# HoodBoard_V1.net
KiCad netlist of a schematic drawn in EAGLE
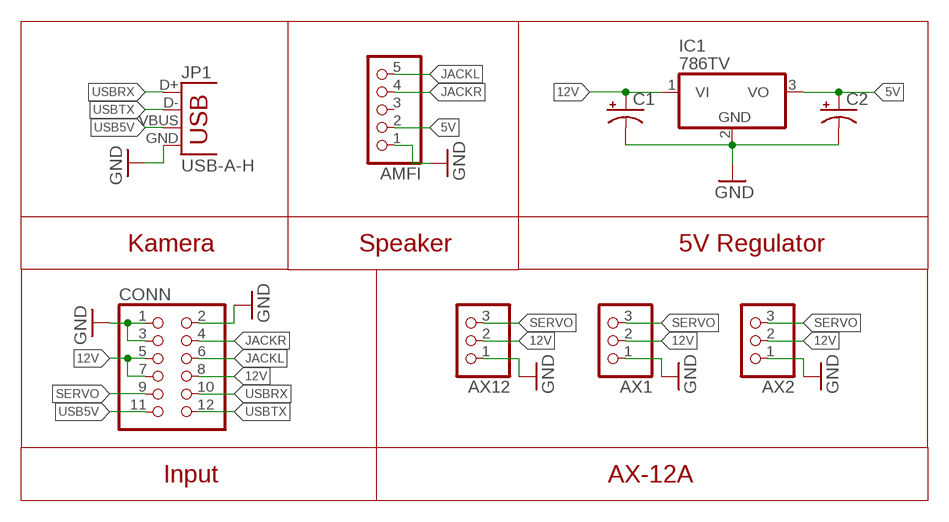
[diagram p0: schematic, sheet 1]

(export (version "E")
  (design (tool "Eeschema 10.0.6"))
  (components
    (comp (ref "AMFI")
      (value "PINHD-1X5")
      (footprint "eagle-import:1X05")
      (libsource (lib "eagle-import") (part "PINHD-1X5"))
    )
    (comp (ref "AX1")
      (value "PINHD-1X3")
      (footprint "eagle-import:1X03")
      (libsource (lib "eagle-import") (part "PINHD-1X3"))
    )
    (comp (ref "AX2")
      (value "PINHD-1X3")
      (footprint "eagle-import:1X03")
      (libsource (lib "eagle-import") (part "PINHD-1X3"))
    )
    (comp (ref "AX12")
      (value "PINHD-1X3")
      (footprint "eagle-import:1X03")
      (libsource (lib "eagle-import") (part "PINHD-1X3"))
    )
    (comp (ref "C1")
      (value "10UF-25V-20%(PTH)")
      (footprint "eagle-import:CPOL-RADIAL-10UF-25V")
      (libsource (lib "eagle-import") (part "10UF-25V-20%(PTH)"))
    )
    (comp (ref "C2")
      (value "10UF-25V-20%(PTH)")
      (footprint "eagle-import:CPOL-RADIAL-10UF-25V")
      (libsource (lib "eagle-import") (part "10UF-25V-20%(PTH)"))
    )
    (comp (ref "CONN")
      (value "PINHD-2X6")
      (footprint "eagle-import:2X06")
      (libsource (lib "eagle-import") (part "PINHD-2X6"))
    )
    (comp (ref "IC1")
      (value "786TV")
      (footprint "eagle-import:TO220V")
      (libsource (lib "eagle-import") (part "78TV6"))
    )
    (comp (ref "JP1")
      (value "USB-A-H")
      (footprint "eagle-import:USB-A-H")
      (libsource (lib "eagle-import") (part "USB-A-H"))
    )
  )
  (nets
    (net (code "1") (name "5V") (class "Default")
      (node (ref "AMFI") (pin "2") (pinfunction "2_2") (pintype "passive"))
      (node (ref "C2") (pin "1") (pinfunction "+_1") (pintype "passive"))
      (node (ref "IC1") (pin "3") (pinfunction "VO_3") (pintype "passive"))
    )
    (net (code "2") (name "12V") (class "Default")
      (node (ref "AX1") (pin "2") (pinfunction "2_2") (pintype "passive"))
      (node (ref "AX12") (pin "2") (pinfunction "2_2") (pintype "passive"))
      (node (ref "AX2") (pin "2") (pinfunction "2_2") (pintype "passive"))
      (node (ref "C1") (pin "1") (pinfunction "+_1") (pintype "passive"))
      (node (ref "CONN") (pin "5") (pinfunction "5_5") (pintype "passive"))
      (node (ref "CONN") (pin "7") (pinfunction "7_7") (pintype "passive"))
      (node (ref "CONN") (pin "8") (pinfunction "8_8") (pintype "passive"))
      (node (ref "IC1") (pin "1") (pinfunction "VI_1") (pintype "input"))
    )
    (net (code "3") (name "GND") (class "Default")
      (node (ref "AMFI") (pin "1") (pinfunction "1_1") (pintype "passive"))
      (node (ref "AX1") (pin "1") (pinfunction "1_1") (pintype "passive"))
      (node (ref "AX12") (pin "1") (pinfunction "1_1") (pintype "passive"))
      (node (ref "AX2") (pin "1") (pinfunction "1_1") (pintype "passive"))
      (node (ref "C1") (pin "2") (pinfunction "-_2") (pintype "passive"))
      (node (ref "C2") (pin "2") (pinfunction "-_2") (pintype "passive"))
      (node (ref "CONN") (pin "1") (pinfunction "1_1") (pintype "passive"))
      (node (ref "CONN") (pin "2") (pinfunction "2_2") (pintype "passive"))
      (node (ref "CONN") (pin "3") (pinfunction "3_3") (pintype "passive"))
      (node (ref "IC1") (pin "2") (pinfunction "GND_2") (pintype "passive"))
      (node (ref "JP1") (pin "GND") (pinfunction "GND_GND") (pintype "bidirectional"))
    )
    (net (code "4") (name "JACKL") (class "Default")
      (node (ref "AMFI") (pin "5") (pinfunction "5_5") (pintype "passive"))
      (node (ref "CONN") (pin "6") (pinfunction "6_6") (pintype "passive"))
    )
    (net (code "5") (name "JACKR") (class "Default")
      (node (ref "AMFI") (pin "4") (pinfunction "4_4") (pintype "passive"))
      (node (ref "CONN") (pin "4") (pinfunction "4_4") (pintype "passive"))
    )
    (net (code "6") (name "SERVO") (class "Default")
      (node (ref "AX1") (pin "3") (pinfunction "3_3") (pintype "passive"))
      (node (ref "AX12") (pin "3") (pinfunction "3_3") (pintype "passive"))
      (node (ref "AX2") (pin "3") (pinfunction "3_3") (pintype "passive"))
      (node (ref "CONN") (pin "9") (pinfunction "9_9") (pintype "passive"))
    )
    (net (code "7") (name "USB5V") (class "Default")
      (node (ref "CONN") (pin "11") (pinfunction "11_11") (pintype "passive"))
      (node (ref "JP1") (pin "VBUS") (pinfunction "VBUS_VBUS") (pintype "bidirectional"))
    )
    (net (code "8") (name "USBRX") (class "Default")
      (node (ref "CONN") (pin "10") (pinfunction "10_10") (pintype "passive"))
      (node (ref "JP1") (pin "D+") (pinfunction "D+_D+") (pintype "bidirectional"))
    )
    (net (code "9") (name "USBTX") (class "Default")
      (node (ref "CONN") (pin "12") (pinfunction "12_12") (pintype "passive"))
      (node (ref "JP1") (pin "D-") (pinfunction "D-_D-") (pintype "bidirectional"))
    )
    (net (code "10") (name "unconnected-(AMFI-Pad3)") (class "Default")
      (node (ref "AMFI") (pin "3") (pinfunction "3_3") (pintype "passive"))
    )
  )
)
